# 1-Schematic_example_main.net
KiCad netlist of a schematic drawn in EasyEDA
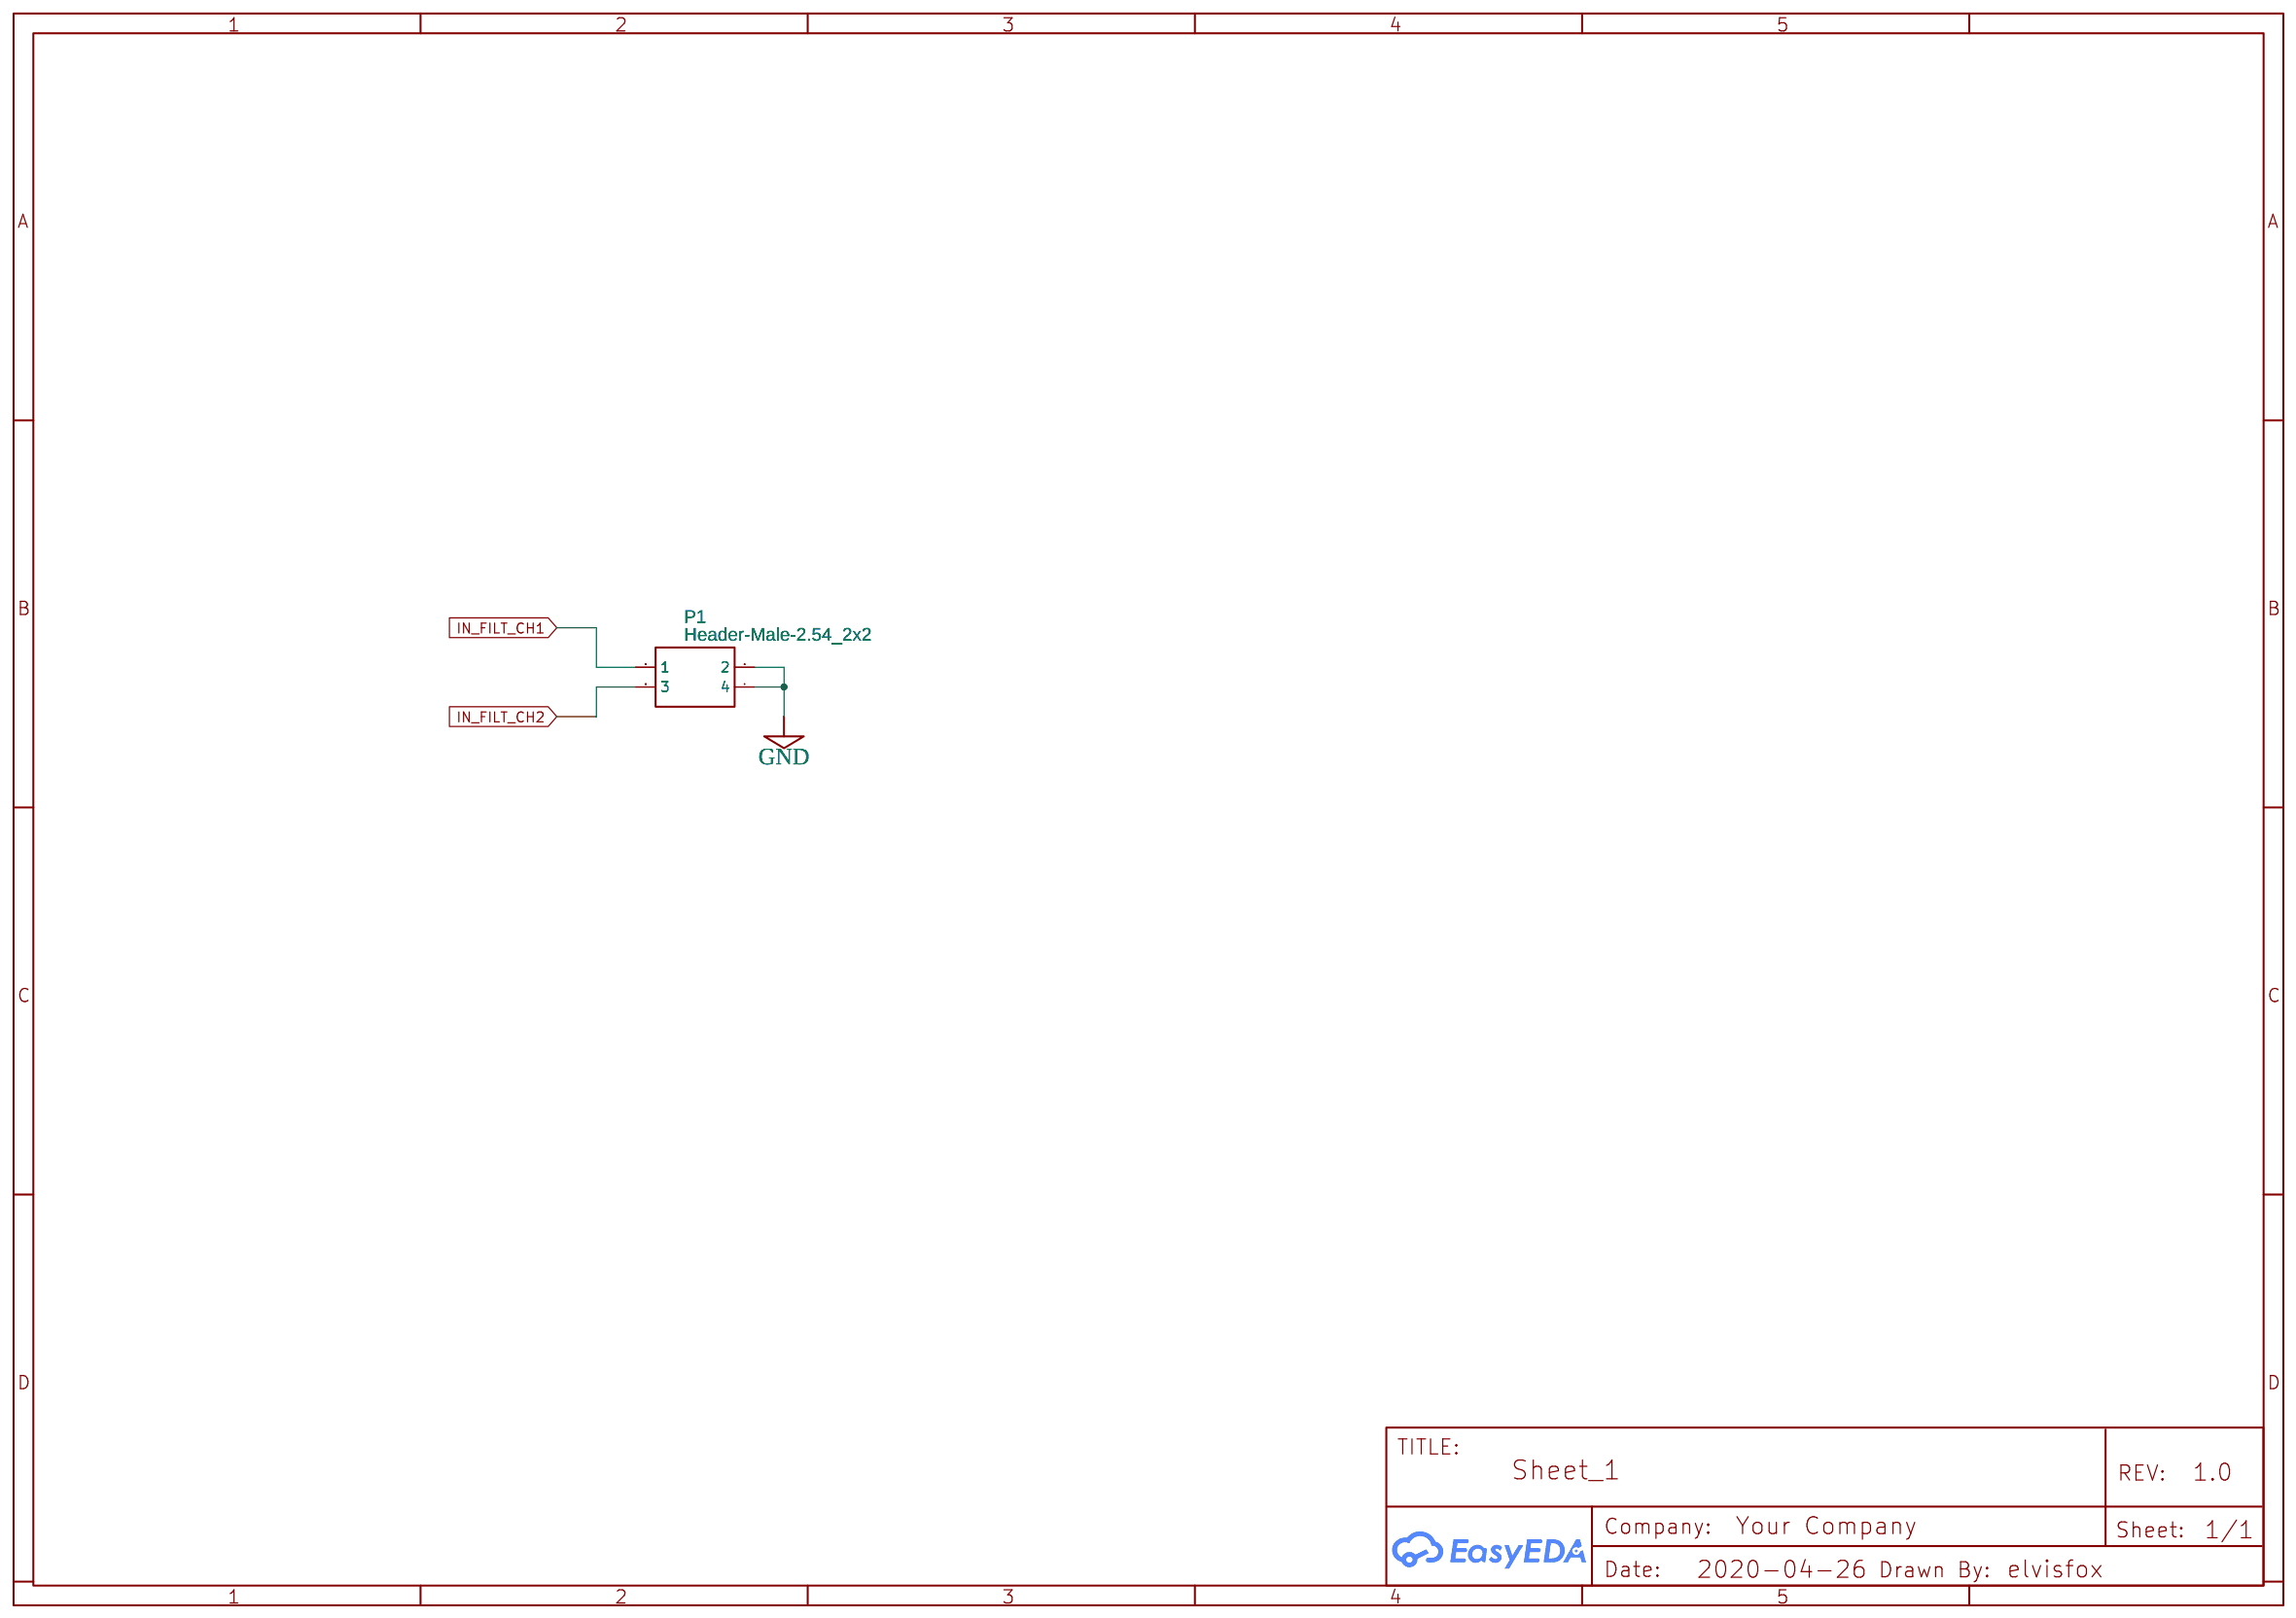
[diagram p0: schematic sheet]

(export (version "E")
  (design (tool "Eeschema 10.0.6"))
  (components
    (comp (ref "P1")
      (value "Header-Male-2.54_2x2")
      (fields
        (field (name "BOM_Manufacturer Part") "Double Rows2.54mm2*2pHeaders  Pins")
        (field (name "BOM_Supplier Part") "C66690")
      )
      (libsource (lib "") (part "Header-Male-2.54_2x2"))
    )
  )
  (nets
    (net (code "1") (name "GND") (class "Default")
      (node (ref "P1") (pin "2") (pinfunction "2_2") (pintype "input"))
      (node (ref "P1") (pin "4") (pinfunction "4_4") (pintype "input"))
    )
    (net (code "2") (name "IN_FILT_CH1") (class "Default")
      (node (ref "P1") (pin "1") (pinfunction "1_1") (pintype "input"))
    )
    (net (code "3") (name "IN_FILT_CH2") (class "Default")
      (node (ref "P1") (pin "3") (pinfunction "3_3") (pintype "input"))
    )
  )
)
